# TCP_IP.net
KiCad netlist of a schematic drawn in Altium Designer
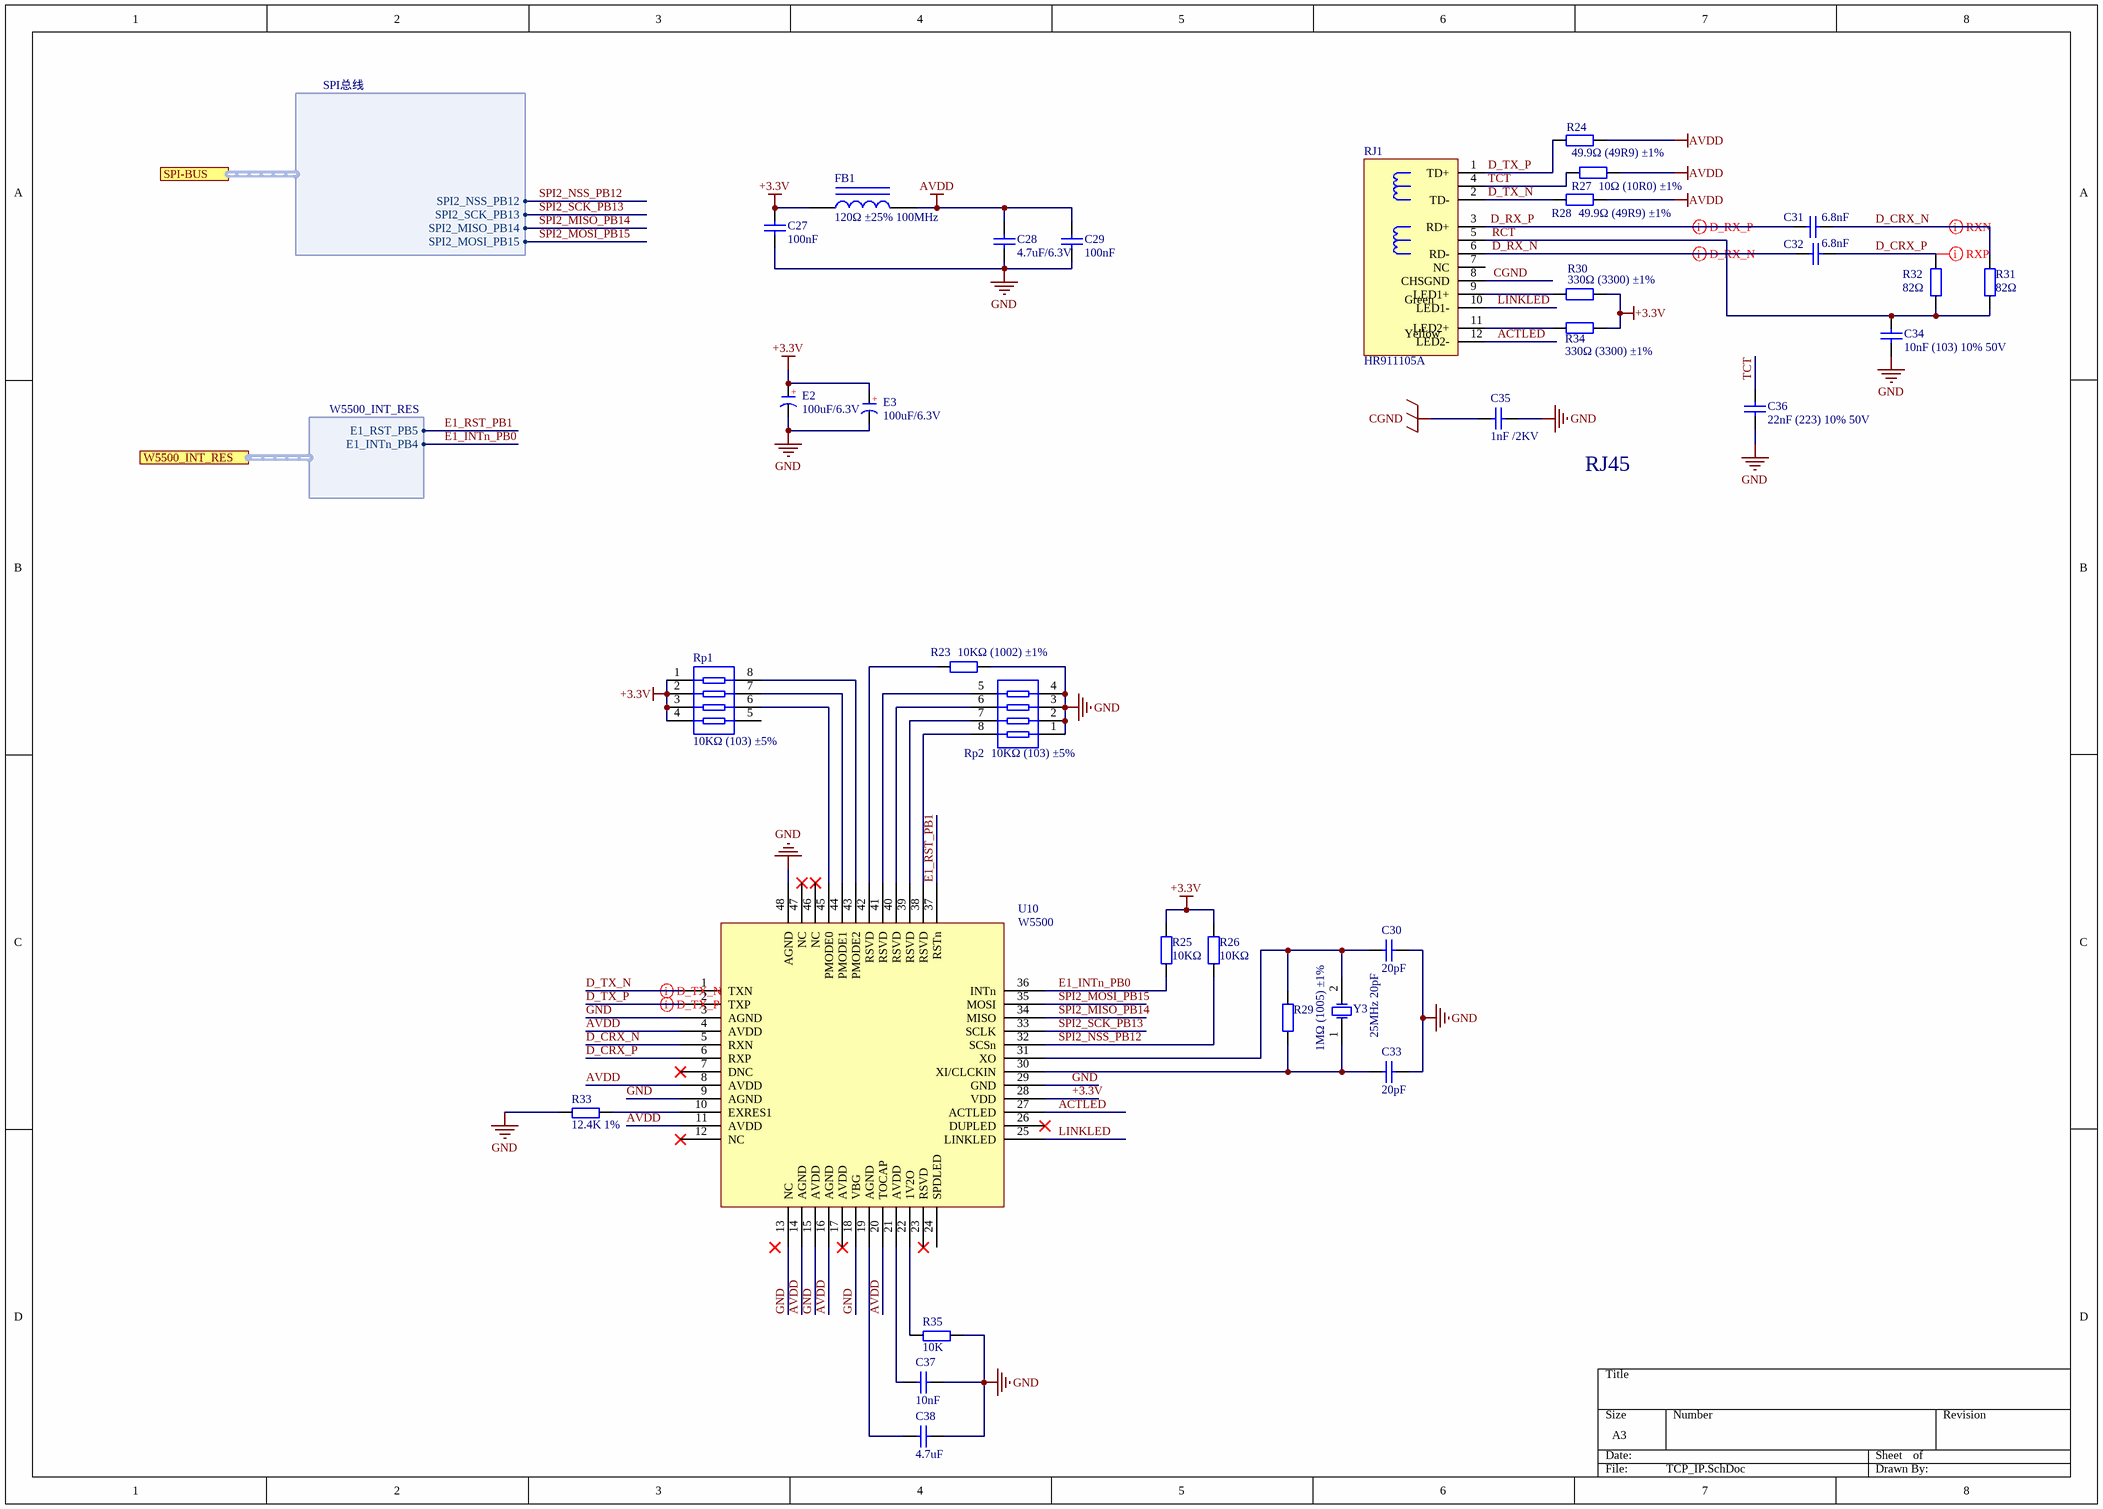
[diagram p0: TCP_IP.SchDoc]

(export (version "E")
  (design (tool "Eeschema 10.0.6"))
  (components
    (comp (ref "C27")
      (value "100nF")
      (footprint "0603_C")
      (description "贴片电容")
      (libsource (lib "Miscellaneous Devices LC") (part "0603 100nF (104) 10% 50V"))
    )
    (comp (ref "C28")
      (value "4.7uF/6.3V")
      (footprint "0603_C")
      (description "贴片电容")
      (libsource (lib "Miscellaneous Devices LC") (part "0603 100nF (104) 10% 50V"))
    )
    (comp (ref "C29")
      (value "100nF")
      (footprint "0603_C")
      (description "贴片电容")
      (libsource (lib "Miscellaneous Devices LC") (part "0603 100nF (104) 10% 50V"))
    )
    (comp (ref "C30")
      (value "20pF")
      (footprint "0603_C")
      (description "贴片电容")
      (libsource (lib "Miscellaneous Devices LC") (part "0603 6pF (6R0) 0.25pF 50V"))
    )
    (comp (ref "C31")
      (value "6.8nF")
      (footprint "0603_C")
      (description "贴片电容")
      (libsource (lib "Miscellaneous Devices LC") (part "0603 6.8nF (682) 10% 50V"))
    )
    (comp (ref "C32")
      (value "6.8nF")
      (footprint "0603_C")
      (description "贴片电容")
      (libsource (lib "Miscellaneous Devices LC") (part "0603 6.8nF (682) 10% 50V"))
    )
    (comp (ref "C33")
      (value "20pF")
      (footprint "0603_C")
      (description "贴片电容")
      (libsource (lib "Miscellaneous Devices LC") (part "0603 6pF (6R0) 0.25pF 50V"))
    )
    (comp (ref "C34")
      (value "10nF (103) 10% 50V")
      (footprint "0603_C")
      (description "贴片电容")
      (libsource (lib "Miscellaneous Devices LC") (part "0603 10nF (103) 10% 50V"))
    )
    (comp (ref "C35")
      (value "1nF /2KV")
      (footprint "1206_C")
      (description "贴片电容")
      (libsource (lib "Miscellaneous Devices LC") (part "1206 470pF (471) 10% 50V"))
    )
    (comp (ref "C36")
      (value "22nF (223) 10% 50V")
      (footprint "0603_C")
      (description "贴片电容")
      (libsource (lib "Miscellaneous Devices LC") (part "0603 22nF (223) 10% 50V"))
    )
    (comp (ref "C37")
      (value "10nF")
      (footprint "0603_C")
      (description "贴片电容")
      (libsource (lib "Miscellaneous Devices LC") (part "0603 10nF (103) 10% 50V"))
    )
    (comp (ref "C38")
      (value "4.7uF")
      (footprint "0603_C")
      (description "贴片电容")
      (libsource (lib "Miscellaneous Devices LC") (part "0603 4.7uF (475) 10% 16V"))
    )
    (comp (ref "E2")
      (value "100uF/6.3V")
      (footprint "CM C(5*5.4)")
      (description "贴片电解电容")
      (fields (field (name "版权归属") "源创客"))
      (libsource (lib "源创客") (part "C-CM"))
    )
    (comp (ref "E3")
      (value "100uF/6.3V")
      (footprint "CM C(5*5.4)")
      (description "贴片电解电容")
      (fields (field (name "版权归属") "源创客"))
      (libsource (lib "源创客") (part "C-CM"))
    )
    (comp (ref "FB1")
      (value "120Ω ±25% 100MHz")
      (footprint "0805_L")
      (description "贴片磁珠")
      (libsource (lib "Miscellaneous Devices LC") (part "0805 600Ω 25% 100MHz"))
    )
    (comp (ref "R23")
      (value "10KΩ (1002) ±1%")
      (footprint "0603_R")
      (description "贴片电阻")
      (libsource (lib "") (part "0603 10KΩ (1002) 1%_1"))
    )
    (comp (ref "R24")
      (value "49.9Ω (49R9) ±1%")
      (footprint "0603_R")
      (description "贴片电阻")
      (libsource (lib "Miscellaneous Devices LC") (part "0603 49.9Ω (49R9) 1%"))
    )
    (comp (ref "R25")
      (value "10KΩ")
      (footprint "0603_R")
      (description "贴片电阻")
      (libsource (lib "Miscellaneous Devices LC") (part "0603 10KΩ (1002) 1%"))
    )
    (comp (ref "R26")
      (value "10KΩ")
      (footprint "0603_R")
      (description "贴片电阻")
      (libsource (lib "Miscellaneous Devices LC") (part "0603 10KΩ (1002) 1%"))
    )
    (comp (ref "R27")
      (value "10Ω (10R0) ±1%")
      (footprint "0603_R")
      (description "贴片电阻")
      (libsource (lib "Miscellaneous Devices LC") (part "0603 10Ω (10R0) 1%"))
    )
    (comp (ref "R28")
      (value "49.9Ω (49R9) ±1%")
      (footprint "0603_R")
      (description "贴片电阻")
      (libsource (lib "Miscellaneous Devices LC") (part "0603 49.9Ω (49R9) 1%"))
    )
    (comp (ref "R29")
      (value "1MΩ (1005) ±1%")
      (footprint "0603_R")
      (description "贴片电阻")
      (libsource (lib "Miscellaneous Devices LC") (part "0603 10MΩ (1005) 1%"))
    )
    (comp (ref "R30")
      (value "330Ω (3300) ±1%")
      (footprint "0603_R")
      (description "贴片电阻")
      (libsource (lib "Miscellaneous Devices LC") (part "0603 330Ω (3300) 1%"))
    )
    (comp (ref "R31")
      (value "82Ω")
      (footprint "0603_R")
      (description "贴片电阻")
      (libsource (lib "Miscellaneous Devices LC") (part "0603 82Ω (82R0) 1%"))
    )
    (comp (ref "R32")
      (value "82Ω")
      (footprint "0603_R")
      (description "贴片电阻")
      (libsource (lib "Miscellaneous Devices LC") (part "0603 82Ω (82R0) 1%"))
    )
    (comp (ref "R33") (value "12.4K 1%") (footprint "0603_R") (libsource (lib "ATK-RM04") (part "R")))
    (comp (ref "R34")
      (value "330Ω (3300) ±1%")
      (footprint "0603_R")
      (description "贴片电阻")
      (libsource (lib "Miscellaneous Devices LC") (part "0603 330Ω (3300) 1%"))
    )
    (comp (ref "R35") (value "10K") (footprint "0603_R") (libsource (lib "ATK-RM04") (part "R")))
    (comp (ref "RJ1")
      (value "HR911105A")
      (footprint "RJ-45A12")
      (description "带灯以太网接口")
      (fields (field (name "版权归属") "源创客"))
      (libsource (lib "源创客") (part "HR911105A"))
    )
    (comp (ref "Rp1")
      (value "10KΩ (103) ±5%")
      (footprint "0603_Rx4")
      (description "贴片排阻")
      (libsource (lib "Miscellaneous Devices LC") (part "0603*4  10KΩ (103) 5%"))
    )
    (comp (ref "Rp2")
      (value "10KΩ (103) ±5%")
      (footprint "0603_Rx4")
      (description "贴片排阻")
      (libsource (lib "Miscellaneous Devices LC") (part "0603*4  10KΩ (103) 5%"))
    )
    (comp (ref "U10")
      (value "W5500")
      (footprint "LQFP-48_7x7x05P")
      (description "以太网")
      (libsource (lib "Miscellaneous Devices LC") (part "W5500"))
    )
    (comp (ref "Y3")
      (value "25MHz 20pF")
      (footprint "XTAL-49S DIP")
      (description "贴片晶振")
      (libsource (lib "Miscellaneous Devices LC") (part "SMD-5032_2P 8MHz 20ppm 20pF"))
    )
  )
  (nets
    (net (code "3") (name "+3.3V") (class "Default")
      (node (ref "C27") (pin "2") (pinfunction "2_2") (pintype "passive"))
      (node (ref "E2") (pin "1") (pinfunction "A_1") (pintype "passive"))
      (node (ref "E3") (pin "1") (pinfunction "A_1") (pintype "passive"))
      (node (ref "FB1") (pin "1") (pinfunction "1_1") (pintype "passive"))
      (node (ref "R25") (pin "2") (pinfunction "2_2") (pintype "passive"))
      (node (ref "R26") (pin "2") (pinfunction "2_2") (pintype "passive"))
      (node (ref "R30") (pin "1") (pinfunction "1_1") (pintype "passive"))
      (node (ref "R34") (pin "1") (pinfunction "1_1") (pintype "passive"))
      (node (ref "Rp1") (pin "1") (pinfunction "1_1") (pintype "passive"))
      (node (ref "Rp1") (pin "2") (pinfunction "2_2") (pintype "passive"))
      (node (ref "Rp1") (pin "3") (pinfunction "3_3") (pintype "passive"))
      (node (ref "Rp1") (pin "4") (pinfunction "4_4") (pintype "passive"))
      (node (ref "U10") (pin "28") (pinfunction "VDD_28") (pintype "passive"))
    )
    (net (code "4") (name "/ACTLED") (class "Default")
      (node (ref "RJ1") (pin "12") (pinfunction "LED2-_12") (pintype "passive"))
      (node (ref "U10") (pin "27") (pinfunction "ACTLED_27") (pintype "passive"))
    )
    (net (code "5") (name "/D_CRX_N") (class "Default")
      (node (ref "C31") (pin "1") (pinfunction "1_1") (pintype "passive"))
      (node (ref "R31") (pin "2") (pinfunction "2_2") (pintype "passive"))
      (node (ref "U10") (pin "5") (pinfunction "RXN_5") (pintype "passive"))
    )
    (net (code "6") (name "/D_CRX_P") (class "Default")
      (node (ref "C32") (pin "1") (pinfunction "1_1") (pintype "passive"))
      (node (ref "R32") (pin "2") (pinfunction "2_2") (pintype "passive"))
      (node (ref "U10") (pin "6") (pinfunction "RXP_6") (pintype "passive"))
    )
    (net (code "7") (name "/D_RX_N") (class "Default")
      (node (ref "C32") (pin "2") (pinfunction "2_2") (pintype "passive"))
      (node (ref "RJ1") (pin "6") (pinfunction "RD-_6") (pintype "passive"))
    )
    (net (code "8") (name "/D_RX_P") (class "Default")
      (node (ref "C31") (pin "2") (pinfunction "2_2") (pintype "passive"))
      (node (ref "RJ1") (pin "3") (pinfunction "RD+_3") (pintype "passive"))
    )
    (net (code "9") (name "/D_TX_N") (class "Default")
      (node (ref "R28") (pin "1") (pinfunction "1_1") (pintype "passive"))
      (node (ref "RJ1") (pin "2") (pinfunction "TD-_2") (pintype "passive"))
      (node (ref "U10") (pin "1") (pinfunction "TXN_1") (pintype "passive"))
    )
    (net (code "10") (name "/D_TX_P") (class "Default")
      (node (ref "R24") (pin "1") (pinfunction "1_1") (pintype "passive"))
      (node (ref "RJ1") (pin "1") (pinfunction "TD+_1") (pintype "passive"))
      (node (ref "U10") (pin "2") (pinfunction "TXP_2") (pintype "passive"))
    )
    (net (code "11") (name "/E1_INTn_PB0") (class "Default")
      (node (ref "R25") (pin "1") (pinfunction "1_1") (pintype "passive"))
      (node (ref "U10") (pin "36") (pinfunction "INTn_36") (pintype "passive"))
    )
    (net (code "12") (name "/E1_RST_PB1") (class "Default")
      (node (ref "U10") (pin "37") (pinfunction "RSTn_37") (pintype "passive"))
    )
    (net (code "13") (name "/LINKLED") (class "Default")
      (node (ref "RJ1") (pin "10") (pinfunction "LED1-_10") (pintype "passive"))
      (node (ref "U10") (pin "25") (pinfunction "LINKLED_25") (pintype "passive"))
    )
    (net (code "14") (name "/RCT") (class "Default")
      (node (ref "C34") (pin "2") (pinfunction "2_2") (pintype "passive"))
      (node (ref "R31") (pin "1") (pinfunction "1_1") (pintype "passive"))
      (node (ref "R32") (pin "1") (pinfunction "1_1") (pintype "passive"))
      (node (ref "RJ1") (pin "5") (pintype "passive"))
    )
    (net (code "15") (name "/SPI2_MISO_PB14") (class "Default")
      (node (ref "U10") (pin "34") (pinfunction "MISO_34") (pintype "passive"))
    )
    (net (code "16") (name "/SPI2_MOSI_PB15") (class "Default")
      (node (ref "U10") (pin "35") (pinfunction "MOSI_35") (pintype "passive"))
    )
    (net (code "17") (name "/SPI2_NSS_PB12") (class "Default")
      (node (ref "R26") (pin "1") (pinfunction "1_1") (pintype "passive"))
      (node (ref "U10") (pin "32") (pinfunction "SCSn_32") (pintype "passive"))
    )
    (net (code "18") (name "/SPI2_SCK_PB13") (class "Default")
      (node (ref "U10") (pin "33") (pinfunction "SCLK_33") (pintype "passive"))
    )
    (net (code "19") (name "/TCT") (class "Default")
      (node (ref "C36") (pin "2") (pinfunction "2_2") (pintype "passive"))
      (node (ref "R27") (pin "2") (pinfunction "2_2") (pintype "passive"))
      (node (ref "RJ1") (pin "4") (pintype "passive"))
    )
    (net (code "22") (name "AVDD") (class "Default")
      (node (ref "C28") (pin "2") (pinfunction "2_2") (pintype "passive"))
      (node (ref "C29") (pin "2") (pinfunction "2_2") (pintype "passive"))
      (node (ref "FB1") (pin "2") (pinfunction "2_2") (pintype "passive"))
      (node (ref "R24") (pin "2") (pinfunction "2_2") (pintype "passive"))
      (node (ref "R27") (pin "1") (pinfunction "1_1") (pintype "passive"))
      (node (ref "R28") (pin "2") (pinfunction "2_2") (pintype "passive"))
      (node (ref "U10") (pin "11") (pinfunction "AVDD_11") (pintype "passive"))
      (node (ref "U10") (pin "14") (pinfunction "AGND_14") (pintype "passive"))
      (node (ref "U10") (pin "16") (pinfunction "AGND_16") (pintype "passive"))
      (node (ref "U10") (pin "20") (pinfunction "TOCAP_20") (pintype "passive"))
      (node (ref "U10") (pin "4") (pinfunction "AVDD_4") (pintype "passive"))
      (node (ref "U10") (pin "8") (pinfunction "AVDD_8") (pintype "passive"))
    )
    (net (code "23") (name "CGND") (class "Default")
      (node (ref "C35") (pin "1") (pinfunction "1_1") (pintype "passive"))
      (node (ref "RJ1") (pin "8") (pinfunction "CHSGND_8") (pintype "passive"))
    )
    (net (code "24") (name "GND") (class "Default")
      (node (ref "C27") (pin "1") (pinfunction "1_1") (pintype "passive"))
      (node (ref "C28") (pin "1") (pinfunction "1_1") (pintype "passive"))
      (node (ref "C29") (pin "1") (pinfunction "1_1") (pintype "passive"))
      (node (ref "C30") (pin "1") (pinfunction "1_1") (pintype "passive"))
      (node (ref "C33") (pin "1") (pinfunction "1_1") (pintype "passive"))
      (node (ref "C34") (pin "1") (pinfunction "1_1") (pintype "passive"))
      (node (ref "C35") (pin "2") (pinfunction "2_2") (pintype "passive"))
      (node (ref "C36") (pin "1") (pinfunction "1_1") (pintype "passive"))
      (node (ref "C37") (pin "1") (pinfunction "1_1") (pintype "passive"))
      (node (ref "C38") (pin "2") (pinfunction "2_2") (pintype "passive"))
      (node (ref "E2") (pin "2") (pinfunction "K_2") (pintype "passive"))
      (node (ref "E3") (pin "2") (pinfunction "K_2") (pintype "passive"))
      (node (ref "R23") (pin "2") (pinfunction "2_2") (pintype "passive"))
      (node (ref "R33") (pin "1") (pintype "passive"))
      (node (ref "R35") (pin "2") (pintype "passive"))
      (node (ref "Rp2") (pin "1") (pinfunction "1_1") (pintype "passive"))
      (node (ref "Rp2") (pin "2") (pinfunction "2_2") (pintype "passive"))
      (node (ref "Rp2") (pin "3") (pinfunction "3_3") (pintype "passive"))
      (node (ref "Rp2") (pin "4") (pinfunction "4_4") (pintype "passive"))
      (node (ref "U10") (pin "13") (pinfunction "NC_13") (pintype "passive"))
      (node (ref "U10") (pin "15") (pinfunction "AVDD_15") (pintype "passive"))
      (node (ref "U10") (pin "18") (pinfunction "VBG_18") (pintype "passive"))
      (node (ref "U10") (pin "29") (pinfunction "GND_29") (pintype "passive"))
      (node (ref "U10") (pin "3") (pinfunction "AGND_3") (pintype "passive"))
      (node (ref "U10") (pin "48") (pinfunction "AGND_48") (pintype "passive"))
      (node (ref "U10") (pin "9") (pinfunction "AGND_9") (pintype "passive"))
    )
    (net (code "25") (name "Net-(C37-Pad2)") (class "Default")
      (node (ref "C37") (pin "2") (pinfunction "2_2") (pintype "passive"))
      (node (ref "U10") (pin "21") (pinfunction "AVDD_21") (pintype "passive"))
    )
    (net (code "26") (name "Net-(C38-Pad1)") (class "Default")
      (node (ref "C38") (pin "1") (pinfunction "1_1") (pintype "passive"))
      (node (ref "U10") (pin "19") (pinfunction "AGND_19") (pintype "passive"))
    )
    (net (code "27") (name "Net-(R23-Pad1)") (class "Default")
      (node (ref "R23") (pin "1") (pinfunction "1_1") (pintype "passive"))
      (node (ref "U10") (pin "42") (pinfunction "RSVD_42") (pintype "passive"))
    )
    (net (code "28") (name "Net-(RJ1-LED1+)") (class "Default")
      (node (ref "R30") (pin "2") (pinfunction "2_2") (pintype "passive"))
      (node (ref "RJ1") (pin "9") (pinfunction "LED1+_9") (pintype "passive"))
    )
    (net (code "29") (name "Net-(RJ1-LED2+)") (class "Default")
      (node (ref "R34") (pin "2") (pinfunction "2_2") (pintype "passive"))
      (node (ref "RJ1") (pin "11") (pinfunction "LED2+_11") (pintype "passive"))
    )
    (net (code "30") (name "Net-(Rp2-Pad5)") (class "Default")
      (node (ref "Rp2") (pin "5") (pinfunction "5_5") (pintype "passive"))
      (node (ref "U10") (pin "41") (pinfunction "RSVD_41") (pintype "passive"))
    )
    (net (code "31") (name "Net-(Rp2-Pad6)") (class "Default")
      (node (ref "Rp2") (pin "6") (pinfunction "6_6") (pintype "passive"))
      (node (ref "U10") (pin "40") (pinfunction "RSVD_40") (pintype "passive"))
    )
    (net (code "32") (name "Net-(Rp2-Pad7)") (class "Default")
      (node (ref "Rp2") (pin "7") (pinfunction "7_7") (pintype "passive"))
      (node (ref "U10") (pin "39") (pinfunction "RSVD_39") (pintype "passive"))
    )
    (net (code "33") (name "Net-(Rp2-Pad8)") (class "Default")
      (node (ref "Rp2") (pin "8") (pinfunction "8_8") (pintype "passive"))
      (node (ref "U10") (pin "38") (pinfunction "RSVD_38") (pintype "passive"))
    )
    (net (code "34") (name "Net-(U10-1V2O)") (class "Default")
      (node (ref "R35") (pin "1") (pintype "passive"))
      (node (ref "U10") (pin "22") (pinfunction "1V2O_22") (pintype "passive"))
    )
    (net (code "35") (name "Net-(U10-EXRES1)") (class "Default")
      (node (ref "R33") (pin "2") (pintype "passive"))
      (node (ref "U10") (pin "10") (pinfunction "EXRES1_10") (pintype "passive"))
    )
    (net (code "36") (name "Net-(U10-PMODE0)") (class "Default")
      (node (ref "Rp1") (pin "6") (pinfunction "6_6") (pintype "passive"))
      (node (ref "U10") (pin "45") (pinfunction "PMODE0_45") (pintype "passive"))
    )
    (net (code "37") (name "Net-(U10-PMODE1)") (class "Default")
      (node (ref "Rp1") (pin "7") (pinfunction "7_7") (pintype "passive"))
      (node (ref "U10") (pin "44") (pinfunction "PMODE1_44") (pintype "passive"))
    )
    (net (code "38") (name "Net-(U10-PMODE2)") (class "Default")
      (node (ref "Rp1") (pin "8") (pinfunction "8_8") (pintype "passive"))
      (node (ref "U10") (pin "43") (pinfunction "PMODE2_43") (pintype "passive"))
    )
    (net (code "39") (name "Net-(U10-XI{slash}CLCKIN)") (class "Default")
      (node (ref "C33") (pin "2") (pinfunction "2_2") (pintype "passive"))
      (node (ref "R29") (pin "1") (pinfunction "1_1") (pintype "passive"))
      (node (ref "U10") (pin "30") (pinfunction "XI/CLCKIN_30") (pintype "passive"))
      (node (ref "Y3") (pin "1") (pinfunction "OSC1_1") (pintype "passive"))
    )
    (net (code "40") (name "Net-(U10-XO)") (class "Default")
      (node (ref "C30") (pin "2") (pinfunction "2_2") (pintype "passive"))
      (node (ref "R29") (pin "2") (pinfunction "2_2") (pintype "passive"))
      (node (ref "U10") (pin "31") (pinfunction "XO_31") (pintype "passive"))
      (node (ref "Y3") (pin "2") (pinfunction "OSC2_2") (pintype "passive"))
    )
    (net (code "41") (name "unconnected-(RJ1-NC-Pad7)") (class "Default")
      (node (ref "RJ1") (pin "7") (pinfunction "NC_7") (pintype "passive"))
    )
    (net (code "42") (name "unconnected-(Rp1-Pad5)") (class "Default")
      (node (ref "Rp1") (pin "5") (pinfunction "5_5") (pintype "passive"))
    )
    (net (code "43") (name "unconnected-(U10-AVDD-Pad17)") (class "Default")
      (node (ref "U10") (pin "17") (pinfunction "AVDD_17") (pintype "passive+no_connect"))
    )
    (net (code "44") (name "unconnected-(U10-DNC-Pad7)") (class "Default")
      (node (ref "U10") (pin "7") (pinfunction "DNC_7") (pintype "passive+no_connect"))
    )
    (net (code "45") (name "unconnected-(U10-DUPLED-Pad26)") (class "Default")
      (node (ref "U10") (pin "26") (pinfunction "DUPLED_26") (pintype "passive+no_connect"))
    )
    (net (code "46") (name "unconnected-(U10-NC-Pad12)") (class "Default")
      (node (ref "U10") (pin "12") (pinfunction "NC_12") (pintype "passive+no_connect"))
    )
    (net (code "47") (name "unconnected-(U10-NC-Pad46)") (class "Default")
      (node (ref "U10") (pin "46") (pinfunction "NC_46") (pintype "passive+no_connect"))
    )
    (net (code "48") (name "unconnected-(U10-NC-Pad47)") (class "Default")
      (node (ref "U10") (pin "47") (pinfunction "NC_47") (pintype "passive+no_connect"))
    )
    (net (code "49") (name "unconnected-(U10-RSVD-Pad23)") (class "Default")
      (node (ref "U10") (pin "23") (pinfunction "RSVD_23") (pintype "passive+no_connect"))
    )
    (net (code "50") (name "unconnected-(U10-SPDLED-Pad24)") (class "Default")
      (node (ref "U10") (pin "24") (pinfunction "SPDLED_24") (pintype "passive"))
    )
  )
)
